# a4_top_dsn.net
KiCad netlist of a schematic drawn in Altium Designer
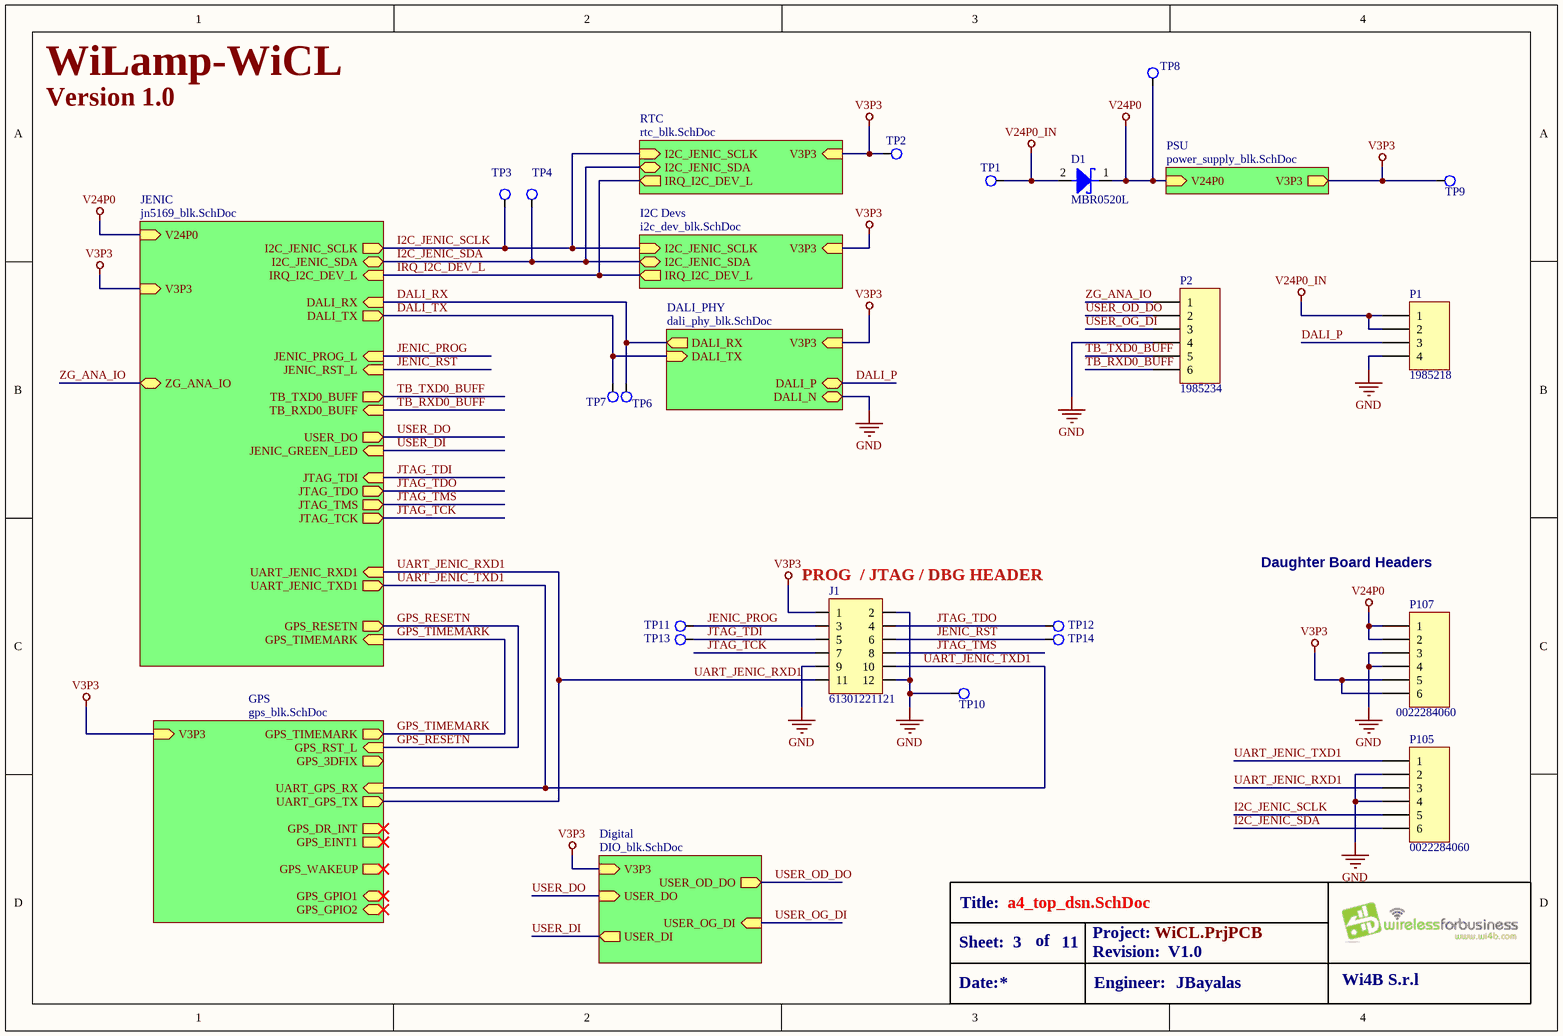
[diagram p0: a4_top_dsn.SchDoc]

(export (version "E")
  (design (tool "Eeschema 10.0.6"))
  (components
    (comp (ref "D1")
      (value "MBR0520L")
      (footprint "SOD123")
      (description "DIODE SCHOTTKY 20V 0.5A SOD123")
      (fields
        (field (name "MANUFACTURER") "Fairchild Semiconductor")
        (field (name "TOLERANCE") "±20%")
        (field (name "MANUFACTURER PART NUMBER") "MBR0520L")
      )
      (libsource (lib "Diode") (part "MBR0520L"))
    )
    (comp (ref "J1")
      (value "61301221121")
      (footprint "61301221121")
      (description "CONN HEADER VERT 12POS 2.54MM")
      (libsource (lib "Connector") (part "61301221121"))
    )
    (comp (ref "P1")
      (value "1985218")
      (footprint "1985218 (4pin)")
      (description "Fixed Terminal Blocks PTSA 1.5/4-3.5-Z")
      (fields (field (name "MPN") "1985218"))
      (libsource (lib "Connector") (part "1985218"))
    )
    (comp (ref "P2")
      (value "1985234")
      (footprint "1985234 (6 PIN)")
      (description "TERM BLOCK PCB 6POS 3.5MM GREEN")
      (fields (field (name "MPN") "1985234"))
      (libsource (lib "Connector") (part "1985234"))
    )
    (comp (ref "P105")
      (value "0022284060")
      (footprint "HDR1X6")
      (description "CONN HEADER 6POS .100 VERT TIN")
      (fields (field (name "MPN") "0022284060"))
      (libsource (lib "WiC_v13") (part "0022284060"))
    )
    (comp (ref "P107")
      (value "0022284060")
      (footprint "HDR1X6")
      (description "CONN HEADER 6POS .100 VERT TIN")
      (fields (field (name "MPN") "0022284060"))
      (libsource (lib "WiC_v13") (part "0022284060"))
    )
    (comp (ref "TP1")
      (value "Test Point_2mm")
      (footprint "Test Point 2mm")
      (description "Test Point 2mm")
      (libsource (lib "Miscellaneous") (part "Test Point_2mm"))
    )
    (comp (ref "TP2")
      (value "Test Point_2mm")
      (footprint "Test Point 2mm")
      (description "Test Point 2mm")
      (libsource (lib "Miscellaneous") (part "Test Point_2mm"))
    )
    (comp (ref "TP3")
      (value "Test Point_2mm")
      (footprint "Test Point 2mm")
      (description "Test Point 2mm")
      (libsource (lib "Miscellaneous") (part "Test Point_2mm"))
    )
    (comp (ref "TP4")
      (value "Test Point_2mm")
      (footprint "Test Point 2mm")
      (description "Test Point 2mm")
      (libsource (lib "Miscellaneous") (part "Test Point_2mm"))
    )
    (comp (ref "TP6")
      (value "Test Point_2mm")
      (footprint "Test Point 2mm")
      (description "Test Point 2mm")
      (libsource (lib "Miscellaneous") (part "Test Point_2mm"))
    )
    (comp (ref "TP7")
      (value "Test Point_2mm")
      (footprint "Test Point 2mm")
      (description "Test Point 2mm")
      (libsource (lib "Miscellaneous") (part "Test Point_2mm"))
    )
    (comp (ref "TP8")
      (value "Test Point_3mm")
      (footprint "Test Point 3mm")
      (description "Test Point 3mm")
      (libsource (lib "Miscellaneous") (part "Test Point_3mm"))
    )
    (comp (ref "TP9")
      (value "Test Point_3mm")
      (footprint "Test Point 3mm")
      (description "Test Point 3mm")
      (libsource (lib "Miscellaneous") (part "Test Point_3mm"))
    )
    (comp (ref "TP10")
      (value "Test Point_3mm")
      (footprint "Test Point 3mm")
      (description "Test Point 3mm")
      (libsource (lib "Miscellaneous") (part "Test Point_3mm"))
    )
    (comp (ref "TP11")
      (value "Test Point_3mm")
      (footprint "Test Point 3mm")
      (description "Test Point 3mm")
      (libsource (lib "Miscellaneous") (part "Test Point_3mm"))
    )
    (comp (ref "TP12")
      (value "Test Point_3mm")
      (footprint "Test Point 3mm")
      (description "Test Point 3mm")
      (libsource (lib "Miscellaneous") (part "Test Point_3mm"))
    )
    (comp (ref "TP13")
      (value "Test Point_3mm")
      (footprint "Test Point 3mm")
      (description "Test Point 3mm")
      (libsource (lib "Miscellaneous") (part "Test Point_3mm"))
    )
    (comp (ref "TP14")
      (value "Test Point_3mm")
      (footprint "Test Point 3mm")
      (description "Test Point 3mm")
      (libsource (lib "Miscellaneous") (part "Test Point_3mm"))
    )
  )
  (nets
    (net (code "1") (name "/DALI_P") (class "Default")
      (node (ref "P1") (pin "3") (pinfunction "3_3") (pintype "passive"))
    )
    (net (code "2") (name "/DALI_RX") (class "Default")
      (node (ref "TP6") (pin "1") (pinfunction "1_1") (pintype "passive"))
    )
    (net (code "3") (name "/DALI_TX") (class "Default")
      (node (ref "TP7") (pin "1") (pinfunction "1_1") (pintype "passive"))
    )
    (net (code "12") (name "/I2C_JENIC_SCLK") (class "Default")
      (node (ref "P105") (pin "5") (pinfunction "5_5") (pintype "passive"))
      (node (ref "TP3") (pin "1") (pinfunction "1_1") (pintype "passive"))
    )
    (net (code "13") (name "/I2C_JENIC_SDA") (class "Default")
      (node (ref "P105") (pin "6") (pinfunction "6_6") (pintype "passive"))
      (node (ref "TP4") (pin "1") (pinfunction "1_1") (pintype "passive"))
    )
    (net (code "15") (name "/JENIC_PROG") (class "Default")
      (node (ref "J1") (pin "3") (pinfunction "3_3") (pintype "passive"))
      (node (ref "TP11") (pin "1") (pinfunction "1_1") (pintype "passive"))
    )
    (net (code "16") (name "/JENIC_RST") (class "Default")
      (node (ref "J1") (pin "6") (pinfunction "6_6") (pintype "passive"))
      (node (ref "TP14") (pin "1") (pinfunction "1_1") (pintype "passive"))
    )
    (net (code "17") (name "/JTAG_TCK") (class "Default")
      (node (ref "J1") (pin "7") (pinfunction "7_7") (pintype "passive"))
    )
    (net (code "18") (name "/JTAG_TDI") (class "Default")
      (node (ref "J1") (pin "5") (pinfunction "5_5") (pintype "passive"))
      (node (ref "TP13") (pin "1") (pinfunction "1_1") (pintype "passive"))
    )
    (net (code "19") (name "/JTAG_TDO") (class "Default")
      (node (ref "J1") (pin "4") (pinfunction "4_4") (pintype "passive"))
      (node (ref "TP12") (pin "1") (pinfunction "1_1") (pintype "passive"))
    )
    (net (code "20") (name "/JTAG_TMS") (class "Default")
      (node (ref "J1") (pin "8") (pinfunction "8_8") (pintype "passive"))
    )
    (net (code "21") (name "/TB_RXD0_BUFF") (class "Default")
      (node (ref "P2") (pin "6") (pinfunction "6_6") (pintype "passive"))
    )
    (net (code "22") (name "/TB_TXD0_BUFF") (class "Default")
      (node (ref "P2") (pin "5") (pinfunction "5_5") (pintype "passive"))
    )
    (net (code "23") (name "/UART_JENIC_RXD1") (class "Default")
      (node (ref "J1") (pin "11") (pinfunction "11_11") (pintype "passive"))
      (node (ref "P105") (pin "3") (pinfunction "3_3") (pintype "passive"))
    )
    (net (code "24") (name "/UART_JENIC_TXD1") (class "Default")
      (node (ref "J1") (pin "10") (pinfunction "10_10") (pintype "passive"))
      (node (ref "P105") (pin "1") (pinfunction "1_1") (pintype "passive"))
    )
    (net (code "27") (name "/USER_OD_DO") (class "Default")
      (node (ref "P2") (pin "2") (pinfunction "2_2") (pintype "passive"))
    )
    (net (code "28") (name "/USER_OG_DI") (class "Default")
      (node (ref "P2") (pin "3") (pinfunction "3_3") (pintype "passive"))
    )
    (net (code "29") (name "/ZG_ANA_IO") (class "Default")
      (node (ref "P2") (pin "1") (pinfunction "1_1") (pintype "passive"))
    )
    (net (code "30") (name "GND") (class "Default")
      (node (ref "J1") (pin "12") (pinfunction "12_12") (pintype "passive"))
      (node (ref "J1") (pin "2") (pinfunction "2_2") (pintype "passive"))
      (node (ref "J1") (pin "9") (pinfunction "9_9") (pintype "passive"))
      (node (ref "P1") (pin "4") (pinfunction "4_4") (pintype "passive"))
      (node (ref "P105") (pin "2") (pinfunction "2_2") (pintype "passive"))
      (node (ref "P105") (pin "4") (pinfunction "4_4") (pintype "passive"))
      (node (ref "P107") (pin "3") (pinfunction "3_3") (pintype "passive"))
      (node (ref "P107") (pin "4") (pinfunction "4_4") (pintype "passive"))
      (node (ref "P2") (pin "4") (pinfunction "4_4") (pintype "passive"))
      (node (ref "TP10") (pin "1") (pinfunction "1_1") (pintype "passive"))
    )
    (net (code "31") (name "V3P3") (class "Default")
      (node (ref "J1") (pin "1") (pinfunction "1_1") (pintype "passive"))
      (node (ref "P107") (pin "5") (pinfunction "5_5") (pintype "passive"))
      (node (ref "P107") (pin "6") (pinfunction "6_6") (pintype "passive"))
      (node (ref "TP2") (pin "1") (pinfunction "1_1") (pintype "passive"))
      (node (ref "TP9") (pin "1") (pinfunction "1_1") (pintype "passive"))
    )
    (net (code "32") (name "V24P0") (class "Default")
      (node (ref "D1") (pin "1") (pinfunction "cathode_1") (pintype "passive"))
      (node (ref "P107") (pin "1") (pinfunction "1_1") (pintype "passive"))
      (node (ref "P107") (pin "2") (pinfunction "2_2") (pintype "passive"))
      (node (ref "TP8") (pin "1") (pinfunction "1_1") (pintype "passive"))
    )
    (net (code "33") (name "V24P0_IN") (class "Default")
      (node (ref "D1") (pin "2") (pinfunction "anode_2") (pintype "passive"))
      (node (ref "P1") (pin "1") (pinfunction "1_1") (pintype "passive"))
      (node (ref "P1") (pin "2") (pinfunction "2_2") (pintype "passive"))
      (node (ref "TP1") (pin "1") (pinfunction "1_1") (pintype "passive"))
    )
  )
)
